# 04_Codec.net
KiCad netlist of a schematic drawn in Altium Designer
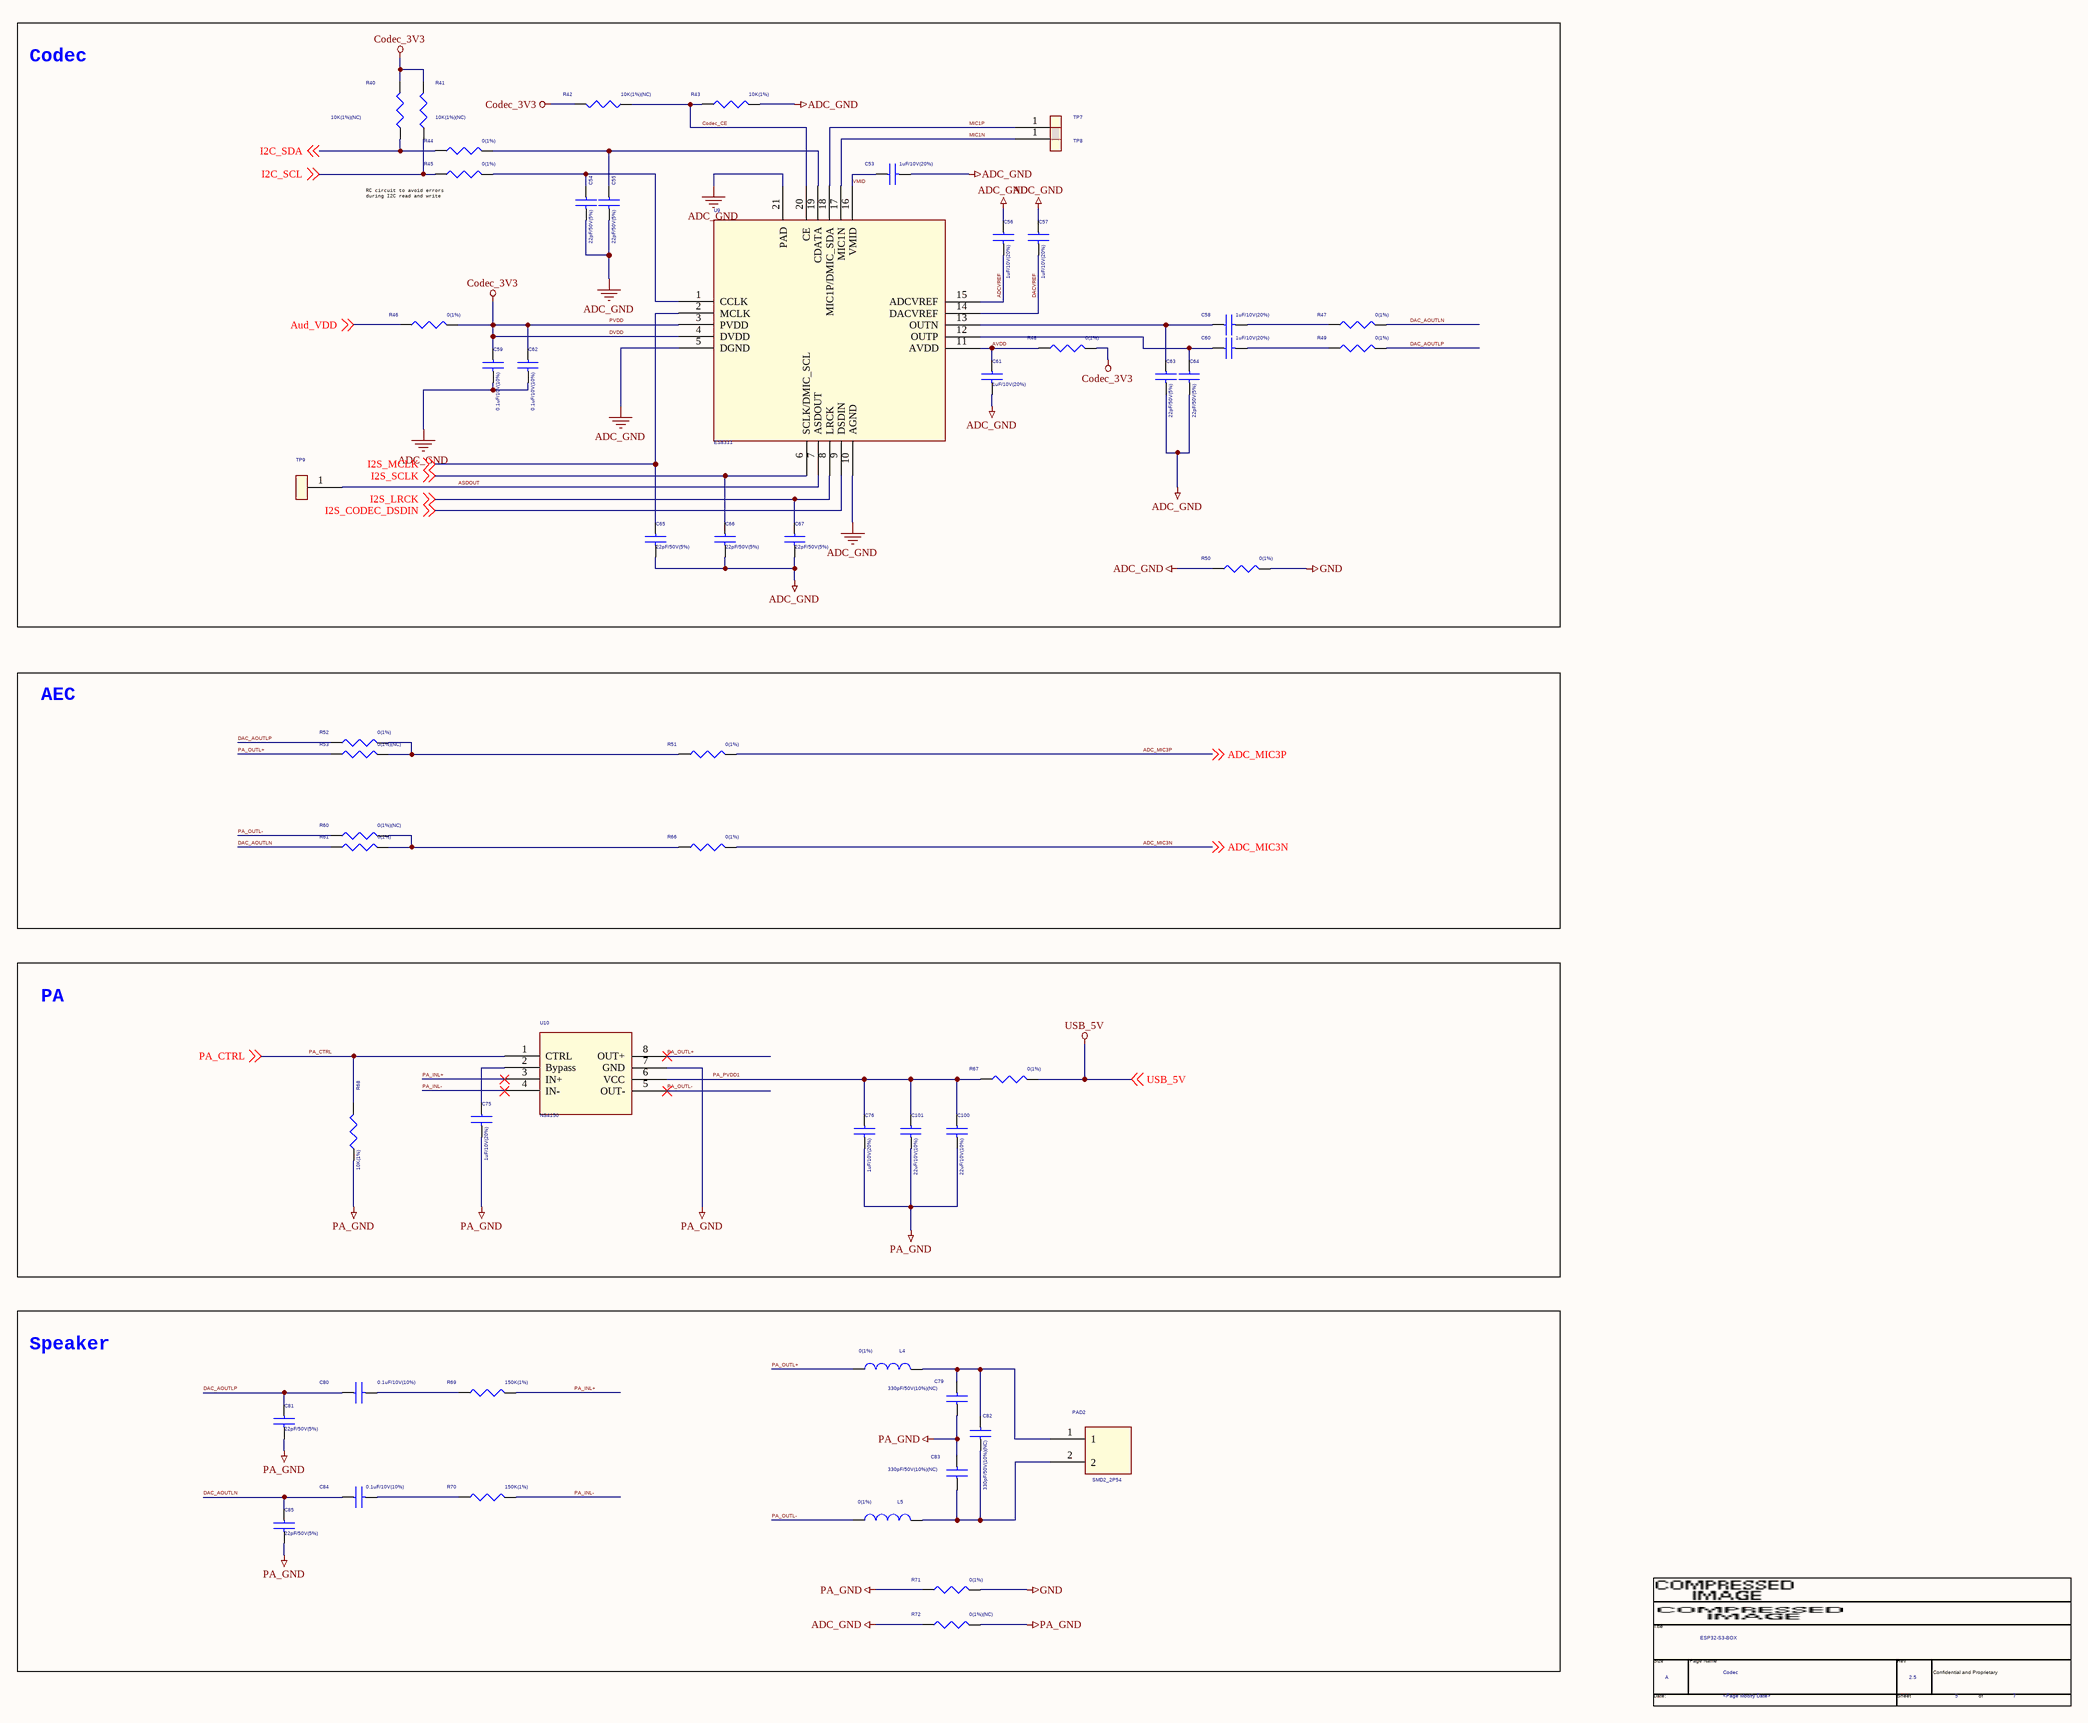
[diagram p0: 04_Codec.SchDoc]

(export (version "E")
  (design (tool "Eeschema 10.0.6"))
  (components
    (comp (ref "C53")
      (value "1uF/10V(20%)")
      (footprint "0201_C")
      (fields (field (name "PART NUMBER") "ES11026103700001"))
      (libsource (lib "*") (part "CAPACITOR"))
    )
    (comp (ref "C54")
      (value "22pF/50V(5%)")
      (footprint "0201_C")
      (fields (field (name "PART NUMBER") "ES11021226520000"))
      (libsource (lib "*") (part "CAPACITOR"))
    )
    (comp (ref "C55")
      (value "22pF/50V(5%)")
      (footprint "0201_C")
      (fields (field (name "PART NUMBER") "ES11021226520000"))
      (libsource (lib "*") (part "CAPACITOR"))
    )
    (comp (ref "C56")
      (value "1uF/10V(20%)")
      (footprint "0201_C")
      (fields (field (name "PART NUMBER") "ES11026103700001"))
      (libsource (lib "*") (part "CAPACITOR"))
    )
    (comp (ref "C57")
      (value "1uF/10V(20%)")
      (footprint "0201_C")
      (fields (field (name "PART NUMBER") "ES11026103700001"))
      (libsource (lib "*") (part "CAPACITOR"))
    )
    (comp (ref "C58")
      (value "1uF/10V(20%)")
      (footprint "0201_C")
      (fields (field (name "PART NUMBER") "ES11026103700001"))
      (libsource (lib "*") (part "CAPACITOR"))
    )
    (comp (ref "C59")
      (value "0.1uF/10V(10%)")
      (footprint "0201_C")
      (fields (field (name "PART NUMBER") "ES11025103610001"))
      (libsource (lib "*") (part "CAPACITOR"))
    )
    (comp (ref "C60")
      (value "1uF/10V(20%)")
      (footprint "0201_C")
      (fields (field (name "PART NUMBER") "ES11026103700001"))
      (libsource (lib "*") (part "CAPACITOR"))
    )
    (comp (ref "C61")
      (value "1uF/10V(20%)")
      (footprint "0201_C")
      (fields (field (name "PART NUMBER") "ES11026103700001"))
      (libsource (lib "*") (part "CAPACITOR"))
    )
    (comp (ref "C62")
      (value "0.1uF/10V(10%)")
      (footprint "0201_C")
      (fields (field (name "PART NUMBER") "ES11025103610001"))
      (libsource (lib "*") (part "CAPACITOR"))
    )
    (comp (ref "C63")
      (value "22pF/50V(5%)")
      (footprint "0201_C")
      (fields (field (name "PART NUMBER") "ES11021226520000"))
      (libsource (lib "*") (part "CAPACITOR"))
    )
    (comp (ref "C64")
      (value "22pF/50V(5%)")
      (footprint "0201_C")
      (fields (field (name "PART NUMBER") "ES11021226520000"))
      (libsource (lib "*") (part "CAPACITOR"))
    )
    (comp (ref "C65")
      (value "22pF/50V(5%)")
      (footprint "0201_C")
      (fields (field (name "PART NUMBER") "ES11021226520000"))
      (libsource (lib "*") (part "CAPACITOR"))
    )
    (comp (ref "C66")
      (value "22pF/50V(5%)")
      (footprint "0201_C")
      (fields (field (name "PART NUMBER") "ES11021226520000"))
      (libsource (lib "*") (part "CAPACITOR"))
    )
    (comp (ref "C67")
      (value "22pF/50V(5%)")
      (footprint "0201_C")
      (fields (field (name "PART NUMBER") "ES11021226520000"))
      (libsource (lib "*") (part "CAPACITOR"))
    )
    (comp (ref "C75")
      (value "1uF/10V(20%)")
      (footprint "0201_C")
      (fields (field (name "PART NUMBER") "ES11026103700001"))
      (libsource (lib "*") (part "CAPACITOR"))
    )
    (comp (ref "C76")
      (value "1uF/10V(20%)")
      (footprint "0201_C")
      (fields (field (name "PART NUMBER") "ES11026103700001"))
      (libsource (lib "*") (part "CAPACITOR"))
    )
    (comp (ref "C79") (value "330pF/50V(10%)(NC)") (footprint "0201_C") (libsource (lib "*") (part "CAP NP")))
    (comp (ref "C80")
      (value "0.1uF/10V(10%)")
      (footprint "0201_C")
      (fields (field (name "PART NUMBER") "ES11025103610001"))
      (libsource (lib "*") (part "CAPACITOR"))
    )
    (comp (ref "C81")
      (value "22pF/50V(5%)")
      (footprint "0201_C")
      (fields (field (name "PART NUMBER") "ES11021226520000"))
      (libsource (lib "*") (part "CAPACITOR"))
    )
    (comp (ref "C82") (value "330pF/50V(10%)(NC)") (footprint "0201_C") (libsource (lib "*") (part "CAP NP")))
    (comp (ref "C83") (value "330pF/50V(10%)(NC)") (footprint "0201_C") (libsource (lib "*") (part "CAP NP")))
    (comp (ref "C84")
      (value "0.1uF/10V(10%)")
      (footprint "0201_C")
      (fields (field (name "PART NUMBER") "ES11025103610001"))
      (libsource (lib "*") (part "CAPACITOR"))
    )
    (comp (ref "C85")
      (value "22pF/50V(5%)")
      (footprint "0201_C")
      (fields (field (name "PART NUMBER") "ES11021226520000"))
      (libsource (lib "*") (part "CAPACITOR"))
    )
    (comp (ref "C100")
      (value "22uF/10V(10%)")
      (footprint "0805_C")
      (fields (field (name "PART NUMBER") "ES11087223720000"))
      (libsource (lib "*") (part "CAPACITOR"))
    )
    (comp (ref "C101")
      (value "22uF/10V(10%)")
      (footprint "0805_C")
      (fields (field (name "PART NUMBER") "ES11087223720000"))
      (libsource (lib "*") (part "CAPACITOR"))
    )
    (comp (ref "L4") (value "0(1%)") (footprint "0603_R") (libsource (lib "*") (part "INDUCTOR")))
    (comp (ref "L5") (value "0(1%)") (footprint "0603_R") (libsource (lib "*") (part "INDUCTOR")))
    (comp (ref "PAD2") (value "SMD2_2P54") (footprint "2pin") (libsource (lib "*") (part "SMD2_2P54")))
    (comp (ref "R40")
      (value "10K(1%)(NC)")
      (footprint "0201_R")
      (fields (field (name "PART NUMBER") "ES21024100000001"))
      (libsource (lib "*") (part "RESISTOR"))
    )
    (comp (ref "R41")
      (value "10K(1%)(NC)")
      (footprint "0201_R")
      (fields (field (name "PART NUMBER") "ES21024100000001"))
      (libsource (lib "*") (part "RESISTOR"))
    )
    (comp (ref "R42")
      (value "10K(1%)(NC)")
      (footprint "0201_R")
      (fields (field (name "PART NUMBER") "ES21024100000001"))
      (libsource (lib "*") (part "RESISTOR"))
    )
    (comp (ref "R43")
      (value "10K(1%)")
      (footprint "0201_R")
      (fields (field (name "PART NUMBER") "ES21024100000001"))
      (libsource (lib "*") (part "RESISTOR"))
    )
    (comp (ref "R44")
      (value "0(1%)")
      (footprint "0201_R")
      (fields (field (name "PART NUMBER") "ES21020000000001"))
      (libsource (lib "*") (part "RESISTOR"))
    )
    (comp (ref "R45")
      (value "0(1%)")
      (footprint "0201_R")
      (fields (field (name "PART NUMBER") "ES21020000000001"))
      (libsource (lib "*") (part "RESISTOR"))
    )
    (comp (ref "R46")
      (value "0(1%)")
      (footprint "0402_R")
      (fields (field (name "PART NUMBER") "ES21040000000001"))
      (libsource (lib "*") (part "RESISTOR"))
    )
    (comp (ref "R47")
      (value "0(1%)")
      (footprint "0201_R")
      (fields (field (name "PART NUMBER") "ES21020000000001"))
      (libsource (lib "*") (part "RESISTOR"))
    )
    (comp (ref "R48")
      (value "0(1%)")
      (footprint "0402_R")
      (fields (field (name "PART NUMBER") "ES21040000000001"))
      (libsource (lib "*") (part "RESISTOR"))
    )
    (comp (ref "R49")
      (value "0(1%)")
      (footprint "0201_R")
      (fields (field (name "PART NUMBER") "ES21020000000001"))
      (libsource (lib "*") (part "RESISTOR"))
    )
    (comp (ref "R50")
      (value "0(1%)")
      (footprint "0402_R")
      (fields (field (name "PART NUMBER") "ES21040000000001"))
      (libsource (lib "*") (part "RESISTOR"))
    )
    (comp (ref "R51")
      (value "0(1%)")
      (footprint "0201_R")
      (fields (field (name "PART NUMBER") "ES21020000000001"))
      (libsource (lib "*") (part "RESISTOR"))
    )
    (comp (ref "R52")
      (value "0(1%)")
      (footprint "0201_R")
      (fields (field (name "PART NUMBER") "ES21020000000001"))
      (libsource (lib "*") (part "RESISTOR"))
    )
    (comp (ref "R53")
      (value "0(1%)(NC)")
      (footprint "0201_R")
      (fields (field (name "PART NUMBER") "ES21020000000001"))
      (libsource (lib "*") (part "RESISTOR"))
    )
    (comp (ref "R60")
      (value "0(1%)(NC)")
      (footprint "0201_R")
      (fields (field (name "PART NUMBER") "ES21020000000001"))
      (libsource (lib "*") (part "RESISTOR"))
    )
    (comp (ref "R61")
      (value "0(1%)")
      (footprint "0201_R")
      (fields (field (name "PART NUMBER") "ES21020000000001"))
      (libsource (lib "*") (part "RESISTOR"))
    )
    (comp (ref "R66")
      (value "0(1%)")
      (footprint "0201_R")
      (fields (field (name "PART NUMBER") "ES21020000000001"))
      (libsource (lib "*") (part "RESISTOR"))
    )
    (comp (ref "R67")
      (value "0(1%)")
      (footprint "0402_R")
      (fields (field (name "PART NUMBER") "ES21040000000001"))
      (libsource (lib "*") (part "RESISTOR"))
    )
    (comp (ref "R68")
      (value "10K(1%)")
      (footprint "0201_R")
      (fields (field (name "PART NUMBER") "ES21024100000001"))
      (libsource (lib "*") (part "RESISTOR"))
    )
    (comp (ref "R69")
      (value "150K(1%)")
      (footprint "0402_R")
      (fields (field (name "PART NUMBER") "ES21045150000001"))
      (libsource (lib "*") (part "RESISTOR"))
    )
    (comp (ref "R70")
      (value "150K(1%)")
      (footprint "0402_R")
      (fields (field (name "PART NUMBER") "ES21045150000001"))
      (libsource (lib "*") (part "RESISTOR"))
    )
    (comp (ref "R71")
      (value "0(1%)")
      (footprint "0402_R")
      (fields (field (name "PART NUMBER") "ES21040000000001"))
      (libsource (lib "*") (part "RESISTOR"))
    )
    (comp (ref "R72")
      (value "0(1%)(NC)")
      (footprint "0402_R")
      (fields (field (name "PART NUMBER") "ES21040000000001"))
      (libsource (lib "*") (part "RESISTOR"))
    )
    (comp (ref "TP7")
      (value "TESTPOINT")
      (footprint "TPC_D40")
      (fields (field (name "PART NUMBER") "ES51990010000000"))
      (libsource (lib "*") (part "TESTPOINT"))
    )
    (comp (ref "TP8")
      (value "TESTPOINT")
      (footprint "TPC_D40")
      (fields (field (name "PART NUMBER") "ES51990010000000"))
      (libsource (lib "*") (part "TESTPOINT"))
    )
    (comp (ref "TP9")
      (value "TESTPOINT")
      (footprint "TPC_D40")
      (fields (field (name "PART NUMBER") "ES51990010000000"))
      (libsource (lib "") (part "TESTPOINT_1"))
    )
    (comp (ref "U9")
      (value "ES8311")
      (footprint "QFN-20_4X4")
      (fields (field (name "PART NUMBER") "ES41181204000000"))
      (libsource (lib "*") (part "ES8311"))
    )
    (comp (ref "U10")
      (value "NS4150")
      (footprint "MSOP-8")
      (fields (field (name "PART NUMBER") "ES41180401000000"))
      (libsource (lib "*") (part "NS4150"))
    )
  )
  (nets
    (net (code "1") (name "/ADCVREF") (class "Default")
      (node (ref "C56") (pin "2") (pinfunction "2_2") (pintype "passive"))
      (node (ref "U9") (pin "15") (pinfunction "ADCVREF_15") (pintype "passive"))
    )
    (net (code "2") (name "/ASDOUT") (class "Default")
      (node (ref "TP9") (pin "1") (pinfunction "1_1") (pintype "passive"))
      (node (ref "U9") (pin "7") (pinfunction "ASDOUT_7") (pintype "passive"))
    )
    (net (code "3") (name "/AVDD") (class "Default")
      (node (ref "C61") (pin "1") (pinfunction "1_1") (pintype "passive"))
      (node (ref "R48") (pin "1") (pinfunction "1_1") (pintype "passive"))
      (node (ref "U9") (pin "11") (pinfunction "AVDD_11") (pintype "passive"))
    )
    (net (code "4") (name "/Codec_CE") (class "Default")
      (node (ref "R42") (pin "1") (pinfunction "1_1") (pintype "passive"))
      (node (ref "R43") (pin "1") (pinfunction "1_1") (pintype "passive"))
      (node (ref "U9") (pin "20") (pinfunction "CE_20") (pintype "passive"))
    )
    (net (code "5") (name "/DACVREF") (class "Default")
      (node (ref "C57") (pin "2") (pinfunction "2_2") (pintype "passive"))
      (node (ref "U9") (pin "14") (pinfunction "DACVREF_14") (pintype "passive"))
    )
    (net (code "6") (name "/DAC_AOUTLN") (class "Default")
      (node (ref "C84") (pin "1") (pinfunction "1_1") (pintype "passive"))
      (node (ref "C85") (pin "1") (pinfunction "1_1") (pintype "passive"))
      (node (ref "R47") (pin "2") (pinfunction "2_2") (pintype "passive"))
      (node (ref "R61") (pin "1") (pinfunction "1_1") (pintype "passive"))
    )
    (net (code "7") (name "/DAC_AOUTLP") (class "Default")
      (node (ref "C80") (pin "1") (pinfunction "1_1") (pintype "passive"))
      (node (ref "C81") (pin "1") (pinfunction "1_1") (pintype "passive"))
      (node (ref "R49") (pin "2") (pinfunction "2_2") (pintype "passive"))
      (node (ref "R52") (pin "1") (pinfunction "1_1") (pintype "passive"))
    )
    (net (code "8") (name "/MIC1N") (class "Default")
      (node (ref "TP8") (pin "1") (pinfunction "1_1") (pintype "passive"))
      (node (ref "U9") (pin "17") (pinfunction "MIC1N_17") (pintype "passive"))
    )
    (net (code "9") (name "/MIC1P") (class "Default")
      (node (ref "TP7") (pin "1") (pinfunction "1_1") (pintype "passive"))
      (node (ref "U9") (pin "18") (pinfunction "MIC1P/DMIC_SDA_18") (pintype "passive"))
    )
    (net (code "10") (name "/PA_INL+") (class "Default")
      (node (ref "R69") (pin "2") (pinfunction "2_2") (pintype "passive"))
      (node (ref "U10") (pin "3") (pinfunction "IN+_3") (pintype "passive"))
    )
    (net (code "11") (name "/PA_INL-") (class "Default")
      (node (ref "R70") (pin "2") (pinfunction "2_2") (pintype "passive"))
      (node (ref "U10") (pin "4") (pinfunction "IN-_4") (pintype "passive"))
    )
    (net (code "12") (name "/PA_OUTL+") (class "Default")
      (node (ref "L4") (pin "2") (pinfunction "2_2") (pintype "passive"))
      (node (ref "R53") (pin "1") (pinfunction "1_1") (pintype "passive"))
      (node (ref "U10") (pin "8") (pinfunction "OUT+_8") (pintype "passive"))
    )
    (net (code "13") (name "/PA_OUTL-") (class "Default")
      (node (ref "L5") (pin "2") (pinfunction "2_2") (pintype "passive"))
      (node (ref "R60") (pin "1") (pinfunction "1_1") (pintype "passive"))
      (node (ref "U10") (pin "5") (pinfunction "OUT-_5") (pintype "passive"))
    )
    (net (code "14") (name "/PA_PVDD1") (class "Default")
      (node (ref "C100") (pin "1") (pinfunction "1_1") (pintype "passive"))
      (node (ref "C101") (pin "1") (pinfunction "1_1") (pintype "passive"))
      (node (ref "C76") (pin "1") (pinfunction "1_1") (pintype "passive"))
      (node (ref "R67") (pin "1") (pinfunction "1_1") (pintype "passive"))
      (node (ref "U10") (pin "6") (pinfunction "VCC_6") (pintype "passive"))
    )
    (net (code "15") (name "/VMID") (class "Default")
      (node (ref "C53") (pin "1") (pinfunction "1_1") (pintype "passive"))
      (node (ref "U9") (pin "16") (pinfunction "VMID_16") (pintype "passive"))
    )
    (net (code "16") (name "ADC_GND") (class "Default")
      (node (ref "C53") (pin "2") (pinfunction "2_2") (pintype "passive"))
      (node (ref "C54") (pin "2") (pinfunction "2_2") (pintype "passive"))
      (node (ref "C55") (pin "2") (pinfunction "2_2") (pintype "passive"))
      (node (ref "C56") (pin "1") (pinfunction "1_1") (pintype "passive"))
      (node (ref "C57") (pin "1") (pinfunction "1_1") (pintype "passive"))
      (node (ref "C59") (pin "2") (pinfunction "2_2") (pintype "passive"))
      (node (ref "C61") (pin "2") (pinfunction "2_2") (pintype "passive"))
      (node (ref "C62") (pin "2") (pinfunction "2_2") (pintype "passive"))
      (node (ref "C63") (pin "2") (pinfunction "2_2") (pintype "passive"))
      (node (ref "C64") (pin "2") (pinfunction "2_2") (pintype "passive"))
      (node (ref "C65") (pin "2") (pinfunction "2_2") (pintype "passive"))
      (node (ref "C66") (pin "2") (pinfunction "2_2") (pintype "passive"))
      (node (ref "C67") (pin "2") (pinfunction "2_2") (pintype "passive"))
      (node (ref "R43") (pin "2") (pinfunction "2_2") (pintype "passive"))
      (node (ref "R50") (pin "1") (pinfunction "1_1") (pintype "passive"))
      (node (ref "R72") (pin "1") (pinfunction "1_1") (pintype "passive"))
      (node (ref "U9") (pin "10") (pinfunction "AGND_10") (pintype "passive"))
      (node (ref "U9") (pin "21") (pinfunction "PAD_21") (pintype "passive"))
      (node (ref "U9") (pin "5") (pinfunction "DGND_5") (pintype "passive"))
    )
    (net (code "17") (name "ADC_MIC3N") (class "Default")
      (node (ref "R66") (pin "2") (pinfunction "2_2") (pintype "passive"))
    )
    (net (code "18") (name "ADC_MIC3P") (class "Default")
      (node (ref "R51") (pin "2") (pinfunction "2_2") (pintype "passive"))
    )
    (net (code "19") (name "Aud_VDD") (class "Default")
      (node (ref "R46") (pin "1") (pinfunction "1_1") (pintype "passive"))
    )
    (net (code "20") (name "Codec_3V3") (class "Default")
      (node (ref "C59") (pin "1") (pinfunction "1_1") (pintype "passive"))
      (node (ref "C62") (pin "1") (pinfunction "1_1") (pintype "passive"))
      (node (ref "R40") (pin "2") (pinfunction "2_2") (pintype "passive"))
      (node (ref "R41") (pin "2") (pinfunction "2_2") (pintype "passive"))
      (node (ref "R42") (pin "2") (pinfunction "2_2") (pintype "passive"))
      (node (ref "R46") (pin "2") (pinfunction "2_2") (pintype "passive"))
      (node (ref "R48") (pin "2") (pinfunction "2_2") (pintype "passive"))
      (node (ref "U9") (pin "3") (pinfunction "PVDD_3") (pintype "passive"))
      (node (ref "U9") (pin "4") (pinfunction "DVDD_4") (pintype "passive"))
    )
    (net (code "21") (name "GND") (class "Default")
      (node (ref "R50") (pin "2") (pinfunction "2_2") (pintype "passive"))
      (node (ref "R71") (pin "2") (pinfunction "2_2") (pintype "passive"))
    )
    (net (code "22") (name "I2C_SCL") (class "Default")
      (node (ref "R41") (pin "1") (pinfunction "1_1") (pintype "passive"))
      (node (ref "R45") (pin "1") (pinfunction "1_1") (pintype "passive"))
    )
    (net (code "23") (name "I2C_SDA") (class "Default")
      (node (ref "R40") (pin "1") (pinfunction "1_1") (pintype "passive"))
      (node (ref "R44") (pin "1") (pinfunction "1_1") (pintype "passive"))
    )
    (net (code "24") (name "I2S_CODEC_DSDIN") (class "Default")
      (node (ref "U9") (pin "9") (pinfunction "DSDIN_9") (pintype "passive"))
    )
    (net (code "25") (name "I2S_LRCK") (class "Default")
      (node (ref "C67") (pin "1") (pinfunction "1_1") (pintype "passive"))
      (node (ref "U9") (pin "8") (pinfunction "LRCK_8") (pintype "passive"))
    )
    (net (code "26") (name "I2S_MCLK") (class "Default")
      (node (ref "C65") (pin "1") (pinfunction "1_1") (pintype "passive"))
      (node (ref "U9") (pin "2") (pinfunction "MCLK_2") (pintype "passive"))
    )
    (net (code "27") (name "I2S_SCLK") (class "Default")
      (node (ref "C66") (pin "1") (pinfunction "1_1") (pintype "passive"))
      (node (ref "U9") (pin "6") (pinfunction "SCLK/DMIC_SCL_6") (pintype "passive"))
    )
    (net (code "28") (name "Net-(C58-Pad2)") (class "Default")
      (node (ref "C58") (pin "2") (pinfunction "2_2") (pintype "passive"))
      (node (ref "R47") (pin "1") (pinfunction "1_1") (pintype "passive"))
    )
    (net (code "29") (name "Net-(C60-Pad2)") (class "Default")
      (node (ref "C60") (pin "2") (pinfunction "2_2") (pintype "passive"))
      (node (ref "R49") (pin "1") (pinfunction "1_1") (pintype "passive"))
    )
    (net (code "30") (name "Net-(C79-Pad2)") (class "Default")
      (node (ref "C79") (pin "2") (pinfunction "2_2") (pintype "passive"))
      (node (ref "C82") (pin "2") (pinfunction "2_2") (pintype "passive"))
      (node (ref "L4") (pin "1") (pinfunction "1_1") (pintype "passive"))
      (node (ref "PAD2") (pin "1") (pinfunction "1_1") (pintype "passive"))
    )
    (net (code "31") (name "Net-(C80-Pad2)") (class "Default")
      (node (ref "C80") (pin "2") (pinfunction "2_2") (pintype "passive"))
      (node (ref "R69") (pin "1") (pinfunction "1_1") (pintype "passive"))
    )
    (net (code "32") (name "Net-(C82-Pad1)") (class "Default")
      (node (ref "C82") (pin "1") (pinfunction "1_1") (pintype "passive"))
      (node (ref "C83") (pin "1") (pinfunction "1_1") (pintype "passive"))
      (node (ref "L5") (pin "1") (pinfunction "1_1") (pintype "passive"))
      (node (ref "PAD2") (pin "2") (pinfunction "2_2") (pintype "passive"))
    )
    (net (code "33") (name "Net-(C84-Pad2)") (class "Default")
      (node (ref "C84") (pin "2") (pinfunction "2_2") (pintype "passive"))
      (node (ref "R70") (pin "1") (pinfunction "1_1") (pintype "passive"))
    )
    (net (code "34") (name "Net-(R51-Pad1)") (class "Default")
      (node (ref "R51") (pin "1") (pinfunction "1_1") (pintype "passive"))
      (node (ref "R52") (pin "2") (pinfunction "2_2") (pintype "passive"))
      (node (ref "R53") (pin "2") (pinfunction "2_2") (pintype "passive"))
    )
    (net (code "35") (name "Net-(R60-Pad2)") (class "Default")
      (node (ref "R60") (pin "2") (pinfunction "2_2") (pintype "passive"))
      (node (ref "R61") (pin "2") (pinfunction "2_2") (pintype "passive"))
      (node (ref "R66") (pin "1") (pinfunction "1_1") (pintype "passive"))
    )
    (net (code "36") (name "Net-(U9-CCLK)") (class "Default")
      (node (ref "C54") (pin "1") (pinfunction "1_1") (pintype "passive"))
      (node (ref "R45") (pin "2") (pinfunction "2_2") (pintype "passive"))
      (node (ref "U9") (pin "1") (pinfunction "CCLK_1") (pintype "passive"))
    )
    (net (code "37") (name "Net-(U9-CDATA)") (class "Default")
      (node (ref "C55") (pin "1") (pinfunction "1_1") (pintype "passive"))
      (node (ref "R44") (pin "2") (pinfunction "2_2") (pintype "passive"))
      (node (ref "U9") (pin "19") (pinfunction "CDATA_19") (pintype "passive"))
    )
    (net (code "38") (name "Net-(U9-OUTN)") (class "Default")
      (node (ref "C58") (pin "1") (pinfunction "1_1") (pintype "passive"))
      (node (ref "C63") (pin "1") (pinfunction "1_1") (pintype "passive"))
      (node (ref "U9") (pin "13") (pinfunction "OUTN_13") (pintype "passive"))
    )
    (net (code "39") (name "Net-(U9-OUTP)") (class "Default")
      (node (ref "C60") (pin "1") (pinfunction "1_1") (pintype "passive"))
      (node (ref "C64") (pin "1") (pinfunction "1_1") (pintype "passive"))
      (node (ref "U9") (pin "12") (pinfunction "OUTP_12") (pintype "passive"))
    )
    (net (code "40") (name "Net-(U10-Bypass)") (class "Default")
      (node (ref "C75") (pin "1") (pinfunction "1_1") (pintype "passive"))
      (node (ref "U10") (pin "2") (pinfunction "Bypass_2") (pintype "passive"))
    )
    (net (code "41") (name "PA_CTRL") (class "Default")
      (node (ref "R68") (pin "2") (pinfunction "2_2") (pintype "passive"))
      (node (ref "U10") (pin "1") (pinfunction "CTRL_1") (pintype "passive"))
    )
    (net (code "42") (name "PA_GND") (class "Default")
      (node (ref "C100") (pin "2") (pinfunction "2_2") (pintype "passive"))
      (node (ref "C101") (pin "2") (pinfunction "2_2") (pintype "passive"))
      (node (ref "C75") (pin "2") (pinfunction "2_2") (pintype "passive"))
      (node (ref "C76") (pin "2") (pinfunction "2_2") (pintype "passive"))
      (node (ref "C79") (pin "1") (pinfunction "1_1") (pintype "passive"))
      (node (ref "C81") (pin "2") (pinfunction "2_2") (pintype "passive"))
      (node (ref "C83") (pin "2") (pinfunction "2_2") (pintype "passive"))
      (node (ref "C85") (pin "2") (pinfunction "2_2") (pintype "passive"))
      (node (ref "R68") (pin "1") (pinfunction "1_1") (pintype "passive"))
      (node (ref "R71") (pin "1") (pinfunction "1_1") (pintype "passive"))
      (node (ref "R72") (pin "2") (pinfunction "2_2") (pintype "passive"))
      (node (ref "U10") (pin "7") (pinfunction "GND_7") (pintype "passive"))
    )
    (net (code "43") (name "USB_5V") (class "Default")
      (node (ref "R67") (pin "2") (pinfunction "2_2") (pintype "passive"))
    )
  )
)
